# P17_USB_3_0_HOST.net
KiCad netlist of a schematic drawn in Altium Designer
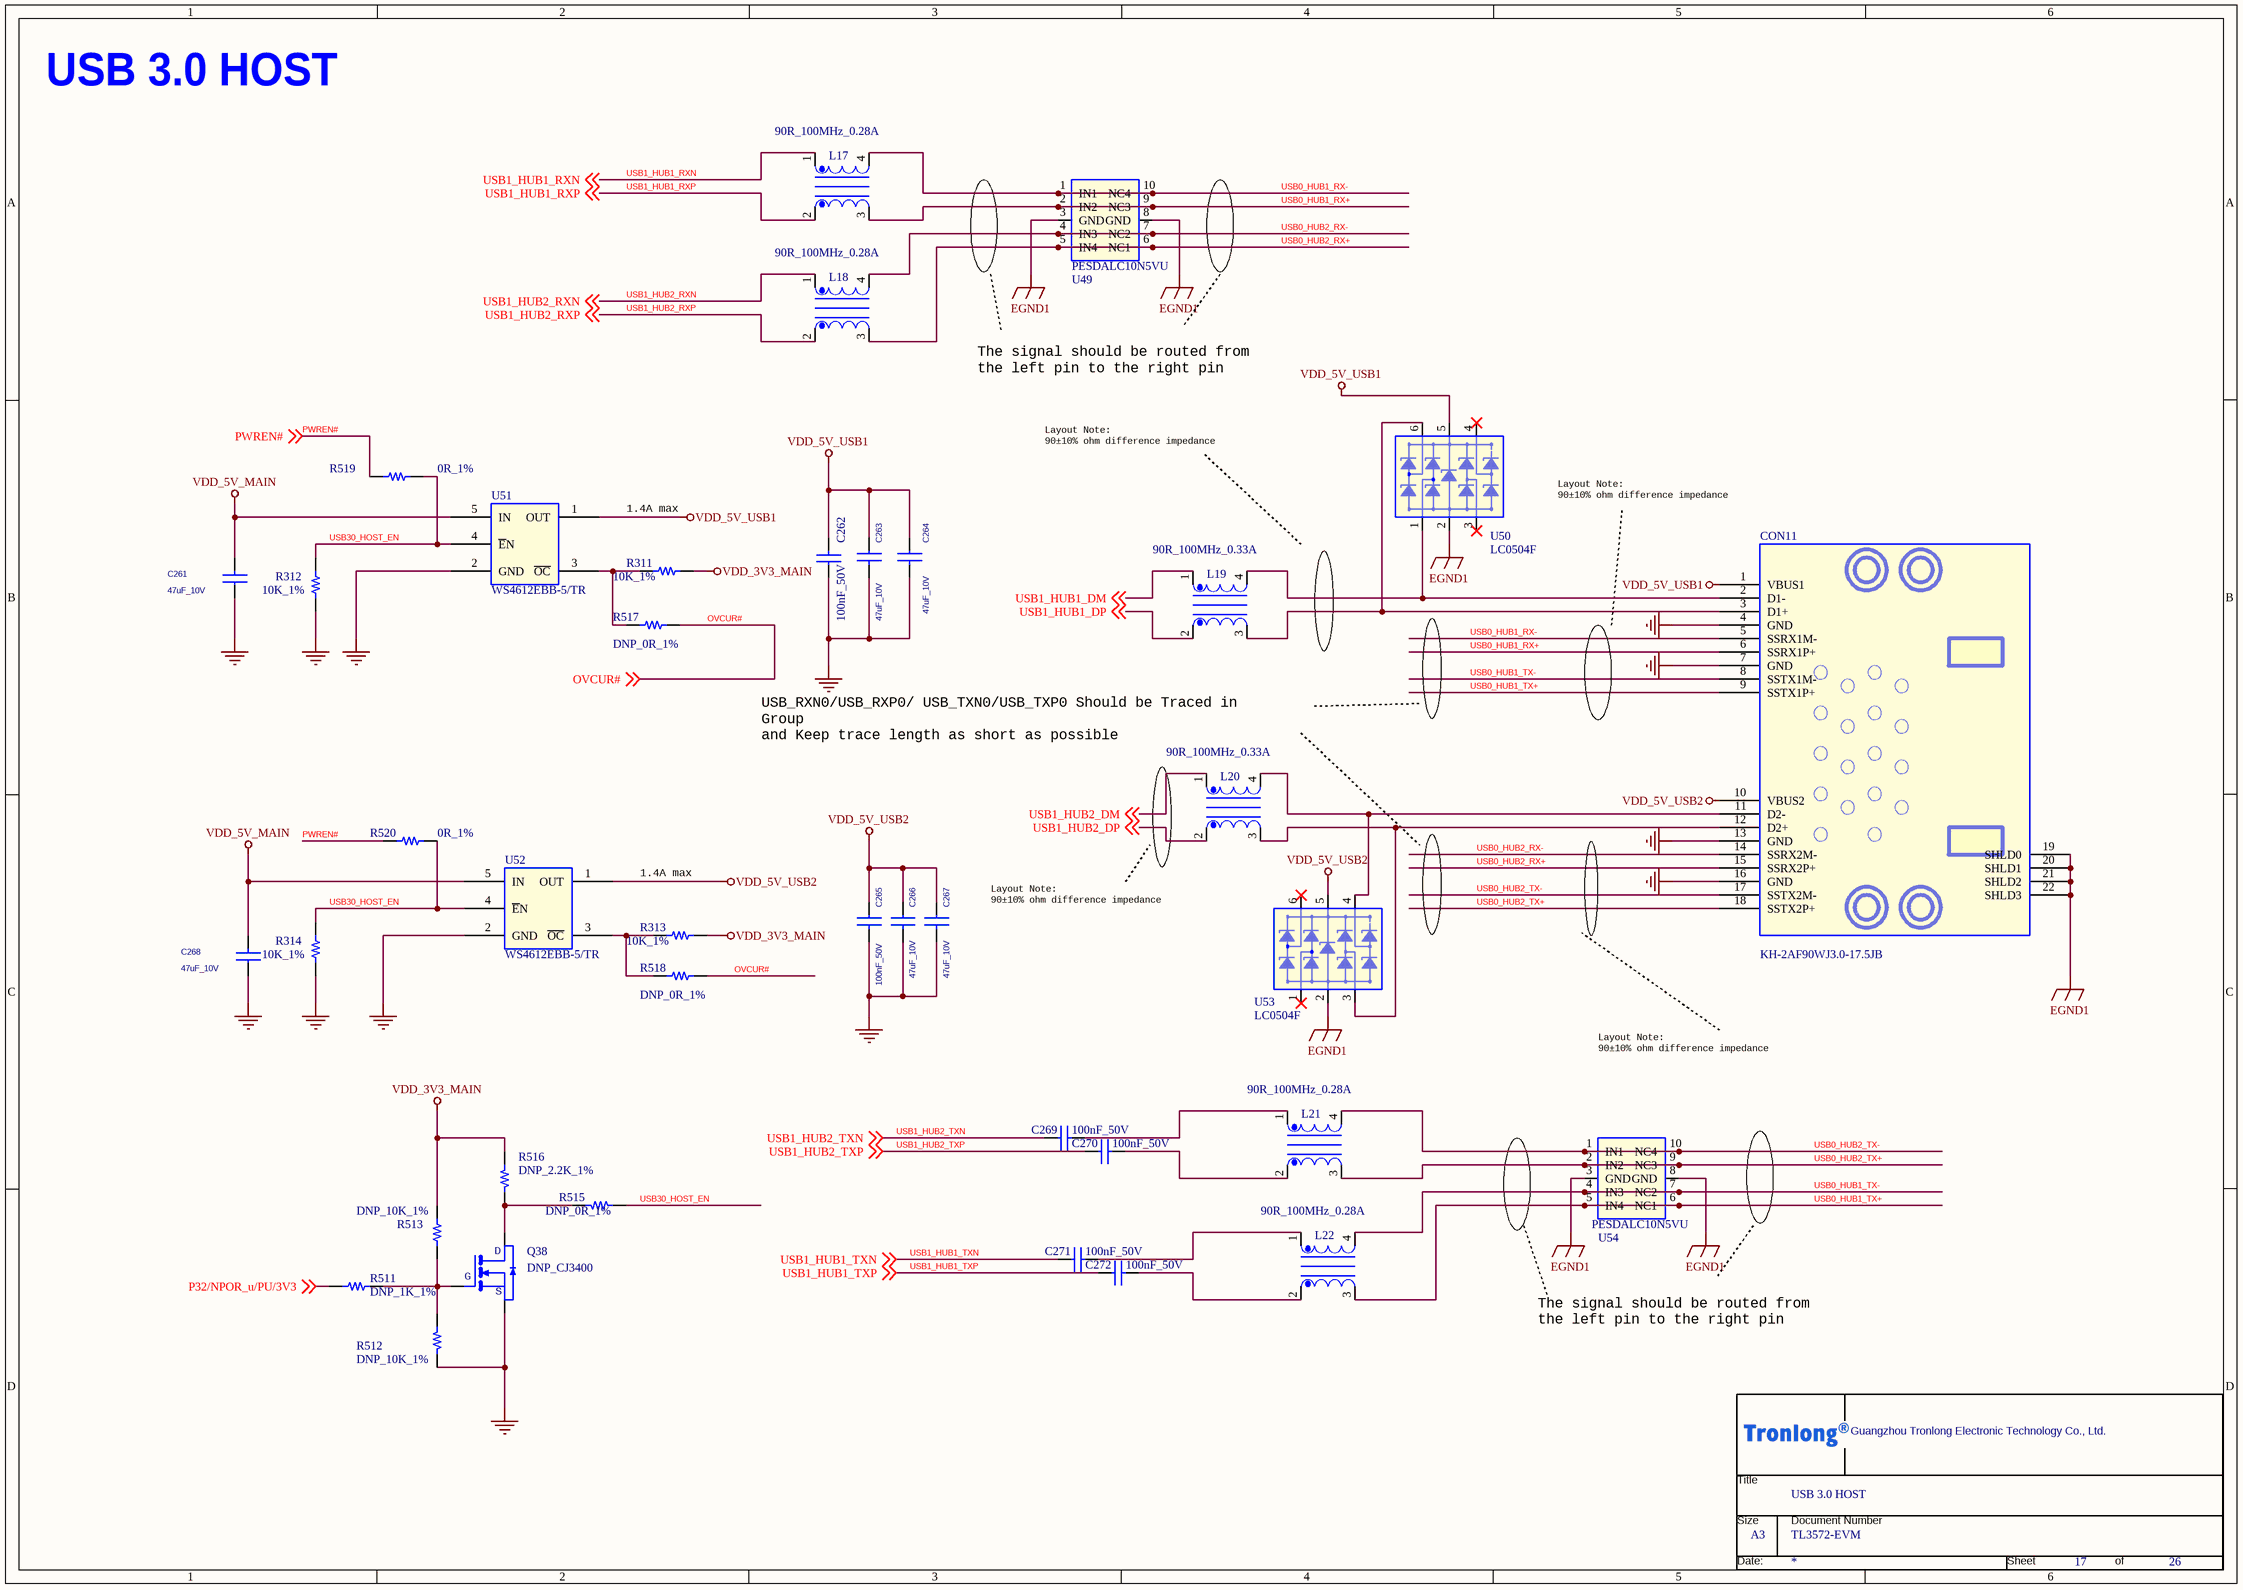
[diagram p0: P17_USB 3.0 HOST.SchDoc]

(export (version "E")
  (design (tool "Eeschema 10.0.6"))
  (components
    (comp (ref "*")
      (value "Tronlong_TITTLE_20211115")
      (fields
        (field (name "DOC") "TL3572-EVM")
        (field (name "TITLE") "USB 3.0 HOST")
        (field (name "ORGNAME") "Guangzhou Tronlong Electronic Technology Co., Ltd.")
        (field (name "PAGE SIZE") "A3")
        (field (name "PAGE NUMBER") "17")
        (field (name "PAGE COUNT") "26")
      )
      (libsource (lib "*") (part "Tronlong_TITTLE_20211115"))
    )
    (comp (ref "C261")
      (value "47uF_10V")
      (footprint "C0805")
      (description "贴片陶瓷电容,47uF,20%,10V,X5R")
      (fields
        (field (name "MANUFACTURER PARTNUMBER") "0805X476M100NT")
        (field (name "MANUFACTURER") "广东风华高新科技股份有限公司（FH）")
      )
      (libsource (lib "*") (part "CAP NP_Dup2"))
    )
    (comp (ref "C262")
      (value "100nF_50V")
      (footprint "C0402")
      (description "贴片陶瓷电容,100nF,10%,50V,X7R")
      (fields
        (field (name "MANUFACTURER PARTNUMBER") "0402B104K500NT")
        (field (name "MANUFACTURER") "广东风华高新科技股份有限公司（FH）")
      )
      (libsource (lib "*") (part "CAP NP_Dup2"))
    )
    (comp (ref "C263")
      (value "47uF_10V")
      (footprint "C0805")
      (description "贴片陶瓷电容,47uF,20%,10V,X5R")
      (fields
        (field (name "MANUFACTURER") "广东风华高新科技股份有限公司（FH）")
        (field (name "MANUFACTURER PARTNUMBER") "0805X476M100NT")
      )
      (libsource (lib "*") (part "CAP NP_Dup2"))
    )
    (comp (ref "C264")
      (value "47uF_10V")
      (footprint "C0805")
      (description "贴片陶瓷电容,47uF,20%,10V,X5R")
      (fields
        (field (name "MANUFACTURER") "广东风华高新科技股份有限公司（FH）")
        (field (name "MANUFACTURER PARTNUMBER") "0805X476M100NT")
      )
      (libsource (lib "*") (part "CAP NP_Dup2"))
    )
    (comp (ref "C265")
      (value "100nF_50V")
      (footprint "C0402")
      (description "贴片陶瓷电容,47uF,20%,10V,X5R")
      (fields
        (field (name "MANUFACTURER PARTNUMBER") "0805X476M100NT")
        (field (name "MANUFACTURER") "广东风华高新科技股份有限公司（FH）")
      )
      (libsource (lib "*") (part "CAP NP_Dup2"))
    )
    (comp (ref "C266")
      (value "47uF_10V")
      (footprint "C0805")
      (description "贴片陶瓷电容,47uF,20%,10V,X5R")
      (fields
        (field (name "MANUFACTURER") "广东风华高新科技股份有限公司（FH）")
        (field (name "MANUFACTURER PARTNUMBER") "0805X476M100NT")
      )
      (libsource (lib "*") (part "CAP NP_Dup2"))
    )
    (comp (ref "C267")
      (value "47uF_10V")
      (footprint "C0805")
      (description "贴片陶瓷电容,47uF,20%,10V,X5R")
      (fields
        (field (name "MANUFACTURER PARTNUMBER") "0805X476M100NT")
        (field (name "MANUFACTURER") "广东风华高新科技股份有限公司（FH）")
      )
      (libsource (lib "*") (part "CAP NP_Dup2"))
    )
    (comp (ref "C268")
      (value "47uF_10V")
      (footprint "C0805")
      (description "贴片陶瓷电容,47uF,20%,10V,X5R")
      (fields
        (field (name "MANUFACTURER") "广东风华高新科技股份有限公司（FH）")
        (field (name "MANUFACTURER PARTNUMBER") "0805X476M100NT")
      )
      (libsource (lib "*") (part "CAP NP_Dup2"))
    )
    (comp (ref "C269")
      (value "100nF_50V")
      (footprint "C0402")
      (description "贴片陶瓷电容,100nF,10%,50V,X7R")
      (fields
        (field (name "MANUFACTURER PARTNUMBER") "0402B104K500NT")
        (field (name "MANUFACTURER") "广东风华高新科技股份有限公司（FH）")
      )
      (libsource (lib "*") (part "CAP NP_Dup2"))
    )
    (comp (ref "C270")
      (value "100nF_50V")
      (footprint "C0402")
      (description "贴片陶瓷电容,100nF,10%,50V,X7R")
      (fields
        (field (name "MANUFACTURER PARTNUMBER") "0402B104K500NT")
        (field (name "MANUFACTURER") "广东风华高新科技股份有限公司（FH）")
      )
      (libsource (lib "*") (part "CAP NP_Dup2"))
    )
    (comp (ref "C271")
      (value "100nF_50V")
      (footprint "C0402")
      (description "贴片陶瓷电容,100nF,10%,50V,X7R")
      (fields
        (field (name "MANUFACTURER") "广东风华高新科技股份有限公司（FH）")
        (field (name "MANUFACTURER PARTNUMBER") "0402B104K500NT")
      )
      (libsource (lib "*") (part "CAP NP_Dup2"))
    )
    (comp (ref "C272")
      (value "100nF_50V")
      (footprint "C0402")
      (description "贴片陶瓷电容,100nF,10%,50V,X7R")
      (fields
        (field (name "MANUFACTURER") "广东风华高新科技股份有限公司（FH）")
        (field (name "MANUFACTURER PARTNUMBER") "0402B104K500NT")
      )
      (libsource (lib "*") (part "CAP NP_Dup2"))
    )
    (comp (ref "CON11")
      (value "KH-2AF90WJ3.0-17.5JB")
      (footprint "con_usb30_a_dual")
      (description "USB A型座,USB3.0,18P,90度,双层,母座,插件")
      (fields (field (name "MANUFACTURER") "深圳市金航标电子有限公司(kinghelm)"))
      (libsource (lib "*") (part "U225-18XN-1VV155-S1"))
    )
    (comp (ref "L17")
      (value "90R_100MHz_0.28A")
      (footprint "SMD-L2012M-4P")
      (description "贴片共模电感,400mΩ,0.28A,20V,90Ω@100MHz")
      (fields
        (field (name "MANUFACTURER PARTNUMBER") "SDCW2012U-2-900TF")
        (field (name "MANUFACTURER") "深圳顺络电子股份有限公司（Sunlord）")
      )
      (libsource (lib "*") (part "TFR_AXA_A_1"))
    )
    (comp (ref "L18")
      (value "90R_100MHz_0.28A")
      (footprint "SMD-L2012M-4P")
      (description "贴片共模电感,400mΩ,0.28A,20V,90Ω@100MHz")
      (fields
        (field (name "MANUFACTURER PARTNUMBER") "SDCW2012U-2-900TF")
        (field (name "MANUFACTURER") "深圳顺络电子股份有限公司（Sunlord）")
      )
      (libsource (lib "*") (part "TFR_AXA_A_1"))
    )
    (comp (ref "L19")
      (value "90R_100MHz_0.33A")
      (footprint "SMD-L2012M-4P")
      (description "贴片共模电感,350mΩ,0.33A,50V,90Ω@100MHz")
      (fields
        (field (name "MANUFACTURER") "深圳顺络电子股份有限公司（Sunlord）")
        (field (name "MANUFACTURER PARTNUMBER") "SDCW2012-2-900TF")
      )
      (libsource (lib "*") (part "TFR_AXA_A_1"))
    )
    (comp (ref "L20")
      (value "90R_100MHz_0.33A")
      (footprint "SMD-L2012M-4P")
      (description "贴片共模电感,350mΩ,0.33A,50V,90Ω@100MHz")
      (fields
        (field (name "MANUFACTURER") "深圳顺络电子股份有限公司（Sunlord）")
        (field (name "MANUFACTURER PARTNUMBER") "SDCW2012-2-900TF")
      )
      (libsource (lib "*") (part "TFR_AXA_A_1"))
    )
    (comp (ref "L21")
      (value "90R_100MHz_0.28A")
      (footprint "SMD-L2012M-4P")
      (description "贴片共模电感,400mΩ,0.28A,20V,90Ω@100MHz")
      (fields
        (field (name "MANUFACTURER PARTNUMBER") "SDCW2012U-2-900TF")
        (field (name "MANUFACTURER") "深圳顺络电子股份有限公司（Sunlord）")
      )
      (libsource (lib "*") (part "TFR_AXA_A_1"))
    )
    (comp (ref "L22")
      (value "90R_100MHz_0.28A")
      (footprint "SMD-L2012M-4P")
      (description "贴片共模电感,400mΩ,0.28A,20V,90Ω@100MHz")
      (fields
        (field (name "MANUFACTURER PARTNUMBER") "SDCW2012U-2-900TF")
        (field (name "MANUFACTURER") "深圳顺络电子股份有限公司（Sunlord）")
      )
      (libsource (lib "*") (part "TFR_AXA_A_1"))
    )
    (comp (ref "Q38")
      (value "DNP_CJ3400")
      (footprint "SOT23-3")
      (description "MOSFET,N沟道,VDSS=30V,VGSS=±12V,ID=5.8A,PD=0.35W,VGS(th)=1.4V")
      (fields
        (field (name "MANUFACTURER") "江苏长晶科技股份有限公司（JSCJ）")
        (field (name "MANUFACTURER PARTNUMBER") "CJ3400")
      )
      (libsource (lib "*") (part "MOSFET N SOT"))
    )
    (comp (ref "R311")
      (value "10K_1%")
      (footprint "R0402")
      (description "贴片电阻,10K,±1%,1/16W")
      (fields
        (field (name "MANUFACTURER PARTNUMBER") "RC-02K1002FT")
        (field (name "MANUFACTURER") "广东风华高新科技股份有限公司（FH）")
      )
      (libsource (lib "*") (part "Resistor_Dup3"))
    )
    (comp (ref "R312")
      (value "10K_1%")
      (footprint "R0402")
      (description "贴片电阻,10K,±1%,1/16W")
      (fields
        (field (name "MANUFACTURER PARTNUMBER") "RC-02K1002FT")
        (field (name "MANUFACTURER") "广东风华高新科技股份有限公司（FH）")
      )
      (libsource (lib "*") (part "Resistor_Dup3"))
    )
    (comp (ref "R313")
      (value "10K_1%")
      (footprint "R0402")
      (description "贴片电阻,10K,±1%,1/16W")
      (fields
        (field (name "MANUFACTURER PARTNUMBER") "RC-02K1002FT")
        (field (name "MANUFACTURER") "广东风华高新科技股份有限公司（FH）")
      )
      (libsource (lib "*") (part "Resistor_Dup3"))
    )
    (comp (ref "R314")
      (value "10K_1%")
      (footprint "R0402")
      (description "贴片电阻,10K,±1%,1/16W")
      (fields
        (field (name "MANUFACTURER PARTNUMBER") "RC-02K1002FT")
        (field (name "MANUFACTURER") "广东风华高新科技股份有限公司（FH）")
      )
      (libsource (lib "*") (part "Resistor_Dup3"))
    )
    (comp (ref "R511")
      (value "DNP_1K_1%")
      (footprint "R0402")
      (description "贴片电阻,1K,±1%,1/16W")
      (fields
        (field (name "MANUFACTURER") "广东风华高新科技股份有限公司（FH）")
        (field (name "MISTRAL PART NO") "110009031036-R")
      )
      (libsource (lib "*") (part "Resistor_Dup3"))
    )
    (comp (ref "R512")
      (value "DNP_10K_1%")
      (footprint "R0402")
      (description "贴片电阻,10K,±1%,1/16W")
      (fields
        (field (name "MANUFACTURER") "广东风华高新科技股份有限公司（FH）")
        (field (name "MANUFACTURER PARTNUMBER") "RC-02K1002FT")
      )
      (libsource (lib "*") (part "Resistor_Dup4"))
    )
    (comp (ref "R513")
      (value "DNP_10K_1%")
      (footprint "R0402")
      (description "贴片电阻,10K,±1%,1/16W")
      (fields
        (field (name "MANUFACTURER PARTNUMBER") "RC-02K1002FT")
        (field (name "MANUFACTURER") "广东风华高新科技股份有限公司（FH）")
      )
      (libsource (lib "*") (part "Resistor_Dup3"))
    )
    (comp (ref "R515")
      (value "DNP_0R_1%")
      (footprint "R0402")
      (description "贴片电阻,0R,±1%,1/16W")
      (fields
        (field (name "MANUFACTURER PARTNUMBER") "RC-02000FT")
        (field (name "MANUFACTURER") "广东风华高新科技股份有限公司（FH）")
      )
      (libsource (lib "*") (part "Resistor_Dup3"))
    )
    (comp (ref "R516")
      (value "DNP_2.2K_1%")
      (footprint "R0402")
      (description "贴片电阻,2.2K,±1%,1/16W")
      (fields
        (field (name "MANUFACTURER") "广东风华高新科技股份有限公司（FH）")
        (field (name "MANUFACTURER PARTNUMBER") "RC-02K2201FT")
      )
      (libsource (lib "*") (part "Resistor_Dup4"))
    )
    (comp (ref "R517")
      (value "DNP_0R_1%")
      (footprint "R0402")
      (description "贴片电阻,0R,±1%,1/16W")
      (fields
        (field (name "MANUFACTURER") "广东风华高新科技股份有限公司（FH）")
        (field (name "MANUFACTURER PARTNUMBER") "RC-02000FT")
      )
      (libsource (lib "*") (part "Resistor_Dup3"))
    )
    (comp (ref "R518")
      (value "DNP_0R_1%")
      (footprint "R0402")
      (description "贴片电阻,0R,±1%,1/16W")
      (fields
        (field (name "MANUFACTURER") "广东风华高新科技股份有限公司（FH）")
        (field (name "MANUFACTURER PARTNUMBER") "RC-02000FT")
      )
      (libsource (lib "*") (part "Resistor_Dup3"))
    )
    (comp (ref "R519")
      (value "0R_1%")
      (footprint "R0402")
      (description "贴片电阻,0R,±1%,1/16W")
      (fields
        (field (name "MANUFACTURER PARTNUMBER") "RC-02000FT")
        (field (name "MANUFACTURER") "广东风华高新科技股份有限公司（FH）")
      )
      (libsource (lib "*") (part "Resistor_Dup3"))
    )
    (comp (ref "R520")
      (value "0R_1%")
      (footprint "R0402")
      (description "贴片电阻,0R,±1%,1/16W")
      (fields
        (field (name "MANUFACTURER") "广东风华高新科技股份有限公司（FH）")
        (field (name "MANUFACTURER PARTNUMBER") "RC-02000FT")
      )
      (libsource (lib "*") (part "Resistor_Dup3"))
    )
    (comp (ref "U49")
      (value "PESDALC10N5VU")
      (footprint "DFN-10-2510")
      (description "ESD二极管,VRWM=5V,VBR=6V,四组,单向,15KV,30KV")
      (fields (field (name "MANUFACTURER") "上海芯导电子科技股份有限公司（Prisemi）"))
      (libsource (lib "*") (part "SU099PGTR"))
    )
    (comp (ref "U50")
      (value "LC0504F")
      (footprint "SOT363")
      (description "ESD二极管,VRWM=5V,VBR=6V,四组,单向,8KV,15KV")
      (fields
        (field (name "MANUFACTURER") "上海雷卯电子科技有限公司（Leiditech）")
        (field (name "MANUFACTURER PART NUMBER") "PRTR5V0U4Y")
      )
      (libsource (lib "*") (part "PRTR5V0U4Y_0"))
    )
    (comp (ref "U51")
      (value "WS4612EBB-5/TR")
      (footprint "SOT23-5")
      (description "限流配电开关,2.5V~5.5V,1.4A")
      (fields (field (name "MANUFACTURER") "上海韦尔半导体股份有限公司（WILLSEMI）"))
      (libsource (lib "*") (part "TPS2041BDGN_0"))
    )
    (comp (ref "U52")
      (value "WS4612EBB-5/TR")
      (footprint "SOT23-5")
      (description "限流配电开关,2.5V~5.5V,1.4A")
      (fields (field (name "MANUFACTURER") "上海韦尔半导体股份有限公司（WILLSEMI）"))
      (libsource (lib "*") (part "TPS2041BDGN_0"))
    )
    (comp (ref "U53")
      (value "LC0504F")
      (footprint "SOT363")
      (description "ESD二极管,VRWM=5V,VBR=6V,四组,单向,8KV,15KV")
      (fields
        (field (name "MANUFACTURER PART NUMBER") "PRTR5V0U4Y")
        (field (name "MANUFACTURER") "上海雷卯电子科技有限公司（Leiditech）")
      )
      (libsource (lib "*") (part "PRTR5V0U4Y_0"))
    )
    (comp (ref "U54")
      (value "PESDALC10N5VU")
      (footprint "DFN-10-2510")
      (description "ESD二极管,VRWM=5V,VBR=6V,四组,单向,15KV,30KV")
      (fields (field (name "MANUFACTURER") "上海芯导电子科技股份有限公司（Prisemi）"))
      (libsource (lib "*") (part "SU099PGTR"))
    )
  )
  (nets
    (net (code "1") (name "/USB0_HUB1_RX+") (class "Default")
      (node (ref "CON11") (pin "6") (pinfunction "SSRX1P+_6") (pintype "passive"))
      (node (ref "L17") (pin "3") (pinfunction "3_3") (pintype "passive"))
      (node (ref "U49") (pin "2") (pinfunction "IN2_2") (pintype "passive"))
      (node (ref "U49") (pin "9") (pinfunction "NC3_9") (pintype "passive"))
    )
    (net (code "2") (name "/USB0_HUB1_RX-") (class "Default")
      (node (ref "CON11") (pin "5") (pinfunction "SSRX1M-_5") (pintype "passive"))
      (node (ref "L17") (pin "4") (pinfunction "4_4") (pintype "passive"))
      (node (ref "U49") (pin "1") (pinfunction "IN1_1") (pintype "passive"))
      (node (ref "U49") (pin "10") (pinfunction "NC4_10") (pintype "passive"))
    )
    (net (code "3") (name "/USB0_HUB1_TX+") (class "Default")
      (node (ref "CON11") (pin "9") (pinfunction "SSTX1P+_9") (pintype "passive"))
      (node (ref "L22") (pin "3") (pinfunction "3_3") (pintype "passive"))
      (node (ref "U54") (pin "5") (pinfunction "IN4_5") (pintype "passive"))
      (node (ref "U54") (pin "6") (pinfunction "NC1_6") (pintype "passive"))
    )
    (net (code "4") (name "/USB0_HUB1_TX-") (class "Default")
      (node (ref "CON11") (pin "8") (pinfunction "SSTX1M-_8") (pintype "passive"))
      (node (ref "L22") (pin "4") (pinfunction "4_4") (pintype "passive"))
      (node (ref "U54") (pin "4") (pinfunction "IN3_4") (pintype "passive"))
      (node (ref "U54") (pin "7") (pinfunction "NC2_7") (pintype "passive"))
    )
    (net (code "5") (name "/USB0_HUB2_RX+") (class "Default")
      (node (ref "CON11") (pin "15") (pinfunction "SSRX2P+_15") (pintype "passive"))
      (node (ref "L18") (pin "3") (pinfunction "3_3") (pintype "passive"))
      (node (ref "U49") (pin "5") (pinfunction "IN4_5") (pintype "passive"))
      (node (ref "U49") (pin "6") (pinfunction "NC1_6") (pintype "passive"))
    )
    (net (code "6") (name "/USB0_HUB2_RX-") (class "Default")
      (node (ref "CON11") (pin "14") (pinfunction "SSRX2M-_14") (pintype "passive"))
      (node (ref "L18") (pin "4") (pinfunction "4_4") (pintype "passive"))
      (node (ref "U49") (pin "4") (pinfunction "IN3_4") (pintype "passive"))
      (node (ref "U49") (pin "7") (pinfunction "NC2_7") (pintype "passive"))
    )
    (net (code "7") (name "/USB0_HUB2_TX+") (class "Default")
      (node (ref "CON11") (pin "18") (pinfunction "SSTX2P+_18") (pintype "passive"))
      (node (ref "L21") (pin "3") (pinfunction "3_3") (pintype "passive"))
      (node (ref "U54") (pin "2") (pinfunction "IN2_2") (pintype "passive"))
      (node (ref "U54") (pin "9") (pinfunction "NC3_9") (pintype "passive"))
    )
    (net (code "8") (name "/USB0_HUB2_TX-") (class "Default")
      (node (ref "CON11") (pin "17") (pinfunction "SSTX2M-_17") (pintype "passive"))
      (node (ref "L21") (pin "4") (pinfunction "4_4") (pintype "passive"))
      (node (ref "U54") (pin "1") (pinfunction "IN1_1") (pintype "passive"))
      (node (ref "U54") (pin "10") (pinfunction "NC4_10") (pintype "passive"))
    )
    (net (code "9") (name "/USB30_HOST_EN") (class "Default")
      (node (ref "R312") (pin "1") (pinfunction "1_1") (pintype "passive"))
      (node (ref "R314") (pin "1") (pinfunction "1_1") (pintype "passive"))
      (node (ref "R515") (pin "2") (pinfunction "2_2") (pintype "passive"))
      (node (ref "R519") (pin "1") (pinfunction "1_1") (pintype "passive"))
      (node (ref "R520") (pin "1") (pinfunction "1_1") (pintype "passive"))
      (node (ref "U51") (pin "4") (pinfunction "~{E}N_4") (pintype "passive"))
      (node (ref "U52") (pin "4") (pinfunction "~{E}N_4") (pintype "passive"))
    )
    (net (code "10") (name "EGND1") (class "Default")
      (node (ref "CON11") (pin "19") (pinfunction "SHLD0_19") (pintype "passive"))
      (node (ref "CON11") (pin "20") (pinfunction "SHLD1_20") (pintype "passive"))
      (node (ref "CON11") (pin "21") (pinfunction "SHLD2_21") (pintype "passive"))
      (node (ref "CON11") (pin "22") (pinfunction "SHLD3_22") (pintype "passive"))
      (node (ref "U49") (pin "3") (pinfunction "GND_3") (pintype "power_in"))
      (node (ref "U49") (pin "8") (pinfunction "GND_8") (pintype "power_in"))
      (node (ref "U50") (pin "2") (pinfunction "2_2") (pintype "passive"))
      (node (ref "U53") (pin "2") (pinfunction "2_2") (pintype "passive"))
      (node (ref "U54") (pin "3") (pinfunction "GND_3") (pintype "power_in"))
      (node (ref "U54") (pin "8") (pinfunction "GND_8") (pintype "power_in"))
    )
    (net (code "11") (name "GND") (class "Default")
      (node (ref "C261") (pin "1") (pinfunction "1_1") (pintype "passive"))
      (node (ref "C262") (pin "1") (pinfunction "1_1") (pintype "passive"))
      (node (ref "C263") (pin "2") (pinfunction "2_2") (pintype "passive"))
      (node (ref "C264") (pin "2") (pinfunction "2_2") (pintype "passive"))
      (node (ref "C265") (pin "2") (pinfunction "2_2") (pintype "passive"))
      (node (ref "C266") (pin "2") (pinfunction "2_2") (pintype "passive"))
      (node (ref "C267") (pin "2") (pinfunction "2_2") (pintype "passive"))
      (node (ref "C268") (pin "1") (pinfunction "1_1") (pintype "passive"))
      (node (ref "CON11") (pin "13") (pinfunction "GND_13") (pintype "power_in"))
      (node (ref "CON11") (pin "16") (pinfunction "GND_16") (pintype "power_in"))
      (node (ref "CON11") (pin "4") (pinfunction "GND_4") (pintype "power_in"))
      (node (ref "CON11") (pin "7") (pinfunction "GND_7") (pintype "power_in"))
      (node (ref "Q38") (pin "2") (pinfunction "E_2") (pintype "passive"))
      (node (ref "R312") (pin "2") (pinfunction "2_2") (pintype "passive"))
      (node (ref "R314") (pin "2") (pinfunction "2_2") (pintype "passive"))
      (node (ref "R512") (pin "2") (pinfunction "2_2") (pintype "passive"))
      (node (ref "U51") (pin "2") (pinfunction "GND_2") (pintype "passive"))
      (node (ref "U52") (pin "2") (pinfunction "GND_2") (pintype "passive"))
    )
    (net (code "12") (name "Net-(C269-Pad2)") (class "Default")
      (node (ref "C269") (pin "2") (pinfunction "2_2") (pintype "passive"))
      (node (ref "L21") (pin "1") (pinfunction "1_1") (pintype "passive"))
    )
    (net (code "13") (name "Net-(C270-Pad2)") (class "Default")
      (node (ref "C270") (pin "2") (pinfunction "2_2") (pintype "passive"))
      (node (ref "L21") (pin "2") (pinfunction "2_2") (pintype "passive"))
    )
    (net (code "14") (name "Net-(C271-Pad2)") (class "Default")
      (node (ref "C271") (pin "2") (pinfunction "2_2") (pintype "passive"))
      (node (ref "L22") (pin "1") (pinfunction "1_1") (pintype "passive"))
    )
    (net (code "15") (name "Net-(C272-Pad2)") (class "Default")
      (node (ref "C272") (pin "2") (pinfunction "2_2") (pintype "passive"))
      (node (ref "L22") (pin "2") (pinfunction "2_2") (pintype "passive"))
    )
    (net (code "16") (name "Net-(CON11-D1+)") (class "Default")
      (node (ref "CON11") (pin "3") (pinfunction "D1+_3") (pintype "passive"))
      (node (ref "L19") (pin "3") (pinfunction "3_3") (pintype "passive"))
      (node (ref "U50") (pin "6") (pinfunction "6_6") (pintype "passive"))
    )
    (net (code "17") (name "Net-(CON11-D1-)") (class "Default")
      (node (ref "CON11") (pin "2") (pinfunction "D1-_2") (pintype "passive"))
      (node (ref "L19") (pin "4") (pinfunction "4_4") (pintype "passive"))
      (node (ref "U50") (pin "1") (pinfunction "1_1") (pintype "passive"))
    )
    (net (code "18") (name "Net-(CON11-D2+)") (class "Default")
      (node (ref "CON11") (pin "12") (pinfunction "D2+_12") (pintype "passive"))
      (node (ref "L20") (pin "3") (pinfunction "3_3") (pintype "passive"))
      (node (ref "U53") (pin "3") (pinfunction "3_3") (pintype "passive"))
    )
    (net (code "19") (name "Net-(CON11-D2-)") (class "Default")
      (node (ref "CON11") (pin "11") (pinfunction "D2-_11") (pintype "passive"))
      (node (ref "L20") (pin "4") (pinfunction "4_4") (pintype "passive"))
      (node (ref "U53") (pin "4") (pinfunction "4_4") (pintype "passive"))
    )
    (net (code "20") (name "Net-(Q38-B)") (class "Default")
      (node (ref "Q38") (pin "1") (pinfunction "B_1") (pintype "passive"))
      (node (ref "R511") (pin "2") (pinfunction "2_2") (pintype "passive"))
      (node (ref "R512") (pin "1") (pinfunction "1_1") (pintype "passive"))
      (node (ref "R513") (pin "2") (pinfunction "2_2") (pintype "passive"))
    )
    (net (code "21") (name "Net-(Q38-C)") (class "Default")
      (node (ref "Q38") (pin "3") (pinfunction "C_3") (pintype "passive"))
      (node (ref "R515") (pin "1") (pinfunction "1_1") (pintype "passive"))
      (node (ref "R516") (pin "2") (pinfunction "2_2") (pintype "passive"))
    )
    (net (code "22") (name "Net-(U51-~{OC})") (class "Default")
      (node (ref "R311") (pin "2") (pinfunction "2_2") (pintype "passive"))
      (node (ref "R517") (pin "2") (pinfunction "2_2") (pintype "passive"))
      (node (ref "U51") (pin "3") (pinfunction "~{OC}_3") (pintype "passive"))
    )
    (net (code "23") (name "Net-(U52-~{OC})") (class "Default")
      (node (ref "R313") (pin "2") (pinfunction "2_2") (pintype "passive"))
      (node (ref "R518") (pin "2") (pinfunction "2_2") (pintype "passive"))
      (node (ref "U52") (pin "3") (pinfunction "~{OC}_3") (pintype "passive"))
    )
    (net (code "24") (name "OVCUR#") (class "Default")
      (node (ref "R517") (pin "1") (pinfunction "1_1") (pintype "passive"))
      (node (ref "R518") (pin "1") (pinfunction "1_1") (pintype "passive"))
    )
    (net (code "25") (name "P32{slash}NPOR_u{slash}PU{slash}3V3") (class "Default")
      (node (ref "R511") (pin "1") (pinfunction "1_1") (pintype "passive"))
    )
    (net (code "26") (name "PWREN#") (class "Default")
      (node (ref "R519") (pin "2") (pinfunction "2_2") (pintype "passive"))
      (node (ref "R520") (pin "2") (pinfunction "2_2") (pintype "passive"))
    )
    (net (code "27") (name "USB1_HUB1_DM") (class "Default")
      (node (ref "L19") (pin "1") (pinfunction "1_1") (pintype "passive"))
    )
    (net (code "28") (name "USB1_HUB1_DP") (class "Default")
      (node (ref "L19") (pin "2") (pinfunction "2_2") (pintype "passive"))
    )
    (net (code "29") (name "USB1_HUB1_RXN") (class "Default")
      (node (ref "L17") (pin "1") (pinfunction "1_1") (pintype "passive"))
    )
    (net (code "30") (name "USB1_HUB1_RXP") (class "Default")
      (node (ref "L17") (pin "2") (pinfunction "2_2") (pintype "passive"))
    )
    (net (code "31") (name "USB1_HUB1_TXN") (class "Default")
      (node (ref "C271") (pin "1") (pinfunction "1_1") (pintype "passive"))
    )
    (net (code "32") (name "USB1_HUB1_TXP") (class "Default")
      (node (ref "C272") (pin "1") (pinfunction "1_1") (pintype "passive"))
    )
    (net (code "33") (name "USB1_HUB2_DM") (class "Default")
      (node (ref "L20") (pin "1") (pinfunction "1_1") (pintype "passive"))
    )
    (net (code "34") (name "USB1_HUB2_DP") (class "Default")
      (node (ref "L20") (pin "2") (pinfunction "2_2") (pintype "passive"))
    )
    (net (code "35") (name "USB1_HUB2_RXN") (class "Default")
      (node (ref "L18") (pin "1") (pinfunction "1_1") (pintype "passive"))
    )
    (net (code "36") (name "USB1_HUB2_RXP") (class "Default")
      (node (ref "L18") (pin "2") (pinfunction "2_2") (pintype "passive"))
    )
    (net (code "37") (name "USB1_HUB2_TXN") (class "Default")
      (node (ref "C269") (pin "1") (pinfunction "1_1") (pintype "passive"))
    )
    (net (code "38") (name "USB1_HUB2_TXP") (class "Default")
      (node (ref "C270") (pin "1") (pinfunction "1_1") (pintype "passive"))
    )
    (net (code "39") (name "VDD_3V3_MAIN") (class "Default")
      (node (ref "R311") (pin "1") (pinfunction "1_1") (pintype "passive"))
      (node (ref "R313") (pin "1") (pinfunction "1_1") (pintype "passive"))
      (node (ref "R513") (pin "1") (pinfunction "1_1") (pintype "passive"))
      (node (ref "R516") (pin "1") (pinfunction "1_1") (pintype "passive"))
    )
    (net (code "40") (name "VDD_5V_MAIN") (class "Default")
      (node (ref "C261") (pin "2") (pinfunction "2_2") (pintype "passive"))
      (node (ref "C268") (pin "2") (pinfunction "2_2") (pintype "passive"))
      (node (ref "U51") (pin "5") (pinfunction "IN_5") (pintype "passive"))
      (node (ref "U52") (pin "5") (pinfunction "IN_5") (pintype "passive"))
    )
    (net (code "41") (name "VDD_5V_USB1") (class "Default")
      (node (ref "C262") (pin "2") (pinfunction "2_2") (pintype "passive"))
      (node (ref "C263") (pin "1") (pinfunction "1_1") (pintype "passive"))
      (node (ref "C264") (pin "1") (pinfunction "1_1") (pintype "passive"))
      (node (ref "CON11") (pin "1") (pinfunction "VBUS1_1") (pintype "power_in"))
      (node (ref "U50") (pin "5") (pinfunction "5_5") (pintype "passive"))
      (node (ref "U51") (pin "1") (pinfunction "OUT_1") (pintype "passive"))
    )
    (net (code "42") (name "VDD_5V_USB2") (class "Default")
      (node (ref "C265") (pin "1") (pinfunction "1_1") (pintype "passive"))
      (node (ref "C266") (pin "1") (pinfunction "1_1") (pintype "passive"))
      (node (ref "C267") (pin "1") (pinfunction "1_1") (pintype "passive"))
      (node (ref "CON11") (pin "10") (pinfunction "VBUS2_10") (pintype "power_in"))
      (node (ref "U52") (pin "1") (pinfunction "OUT_1") (pintype "passive"))
      (node (ref "U53") (pin "5") (pinfunction "5_5") (pintype "passive"))
    )
    (net (code "43") (name "unconnected-(U50-Pad3)") (class "Default")
      (node (ref "U50") (pin "3") (pinfunction "3_3") (pintype "passive+no_connect"))
    )
    (net (code "44") (name "unconnected-(U50-Pad4)") (class "Default")
      (node (ref "U50") (pin "4") (pinfunction "4_4") (pintype "passive+no_connect"))
    )
    (net (code "45") (name "unconnected-(U53-Pad1)") (class "Default")
      (node (ref "U53") (pin "1") (pinfunction "1_1") (pintype "passive+no_connect"))
    )
    (net (code "46") (name "unconnected-(U53-Pad6)") (class "Default")
      (node (ref "U53") (pin "6") (pinfunction "6_6") (pintype "passive+no_connect"))
    )
  )
)
